# 13_HDMI_TX_RTC.net
KiCad netlist of a schematic drawn in Altium Designer
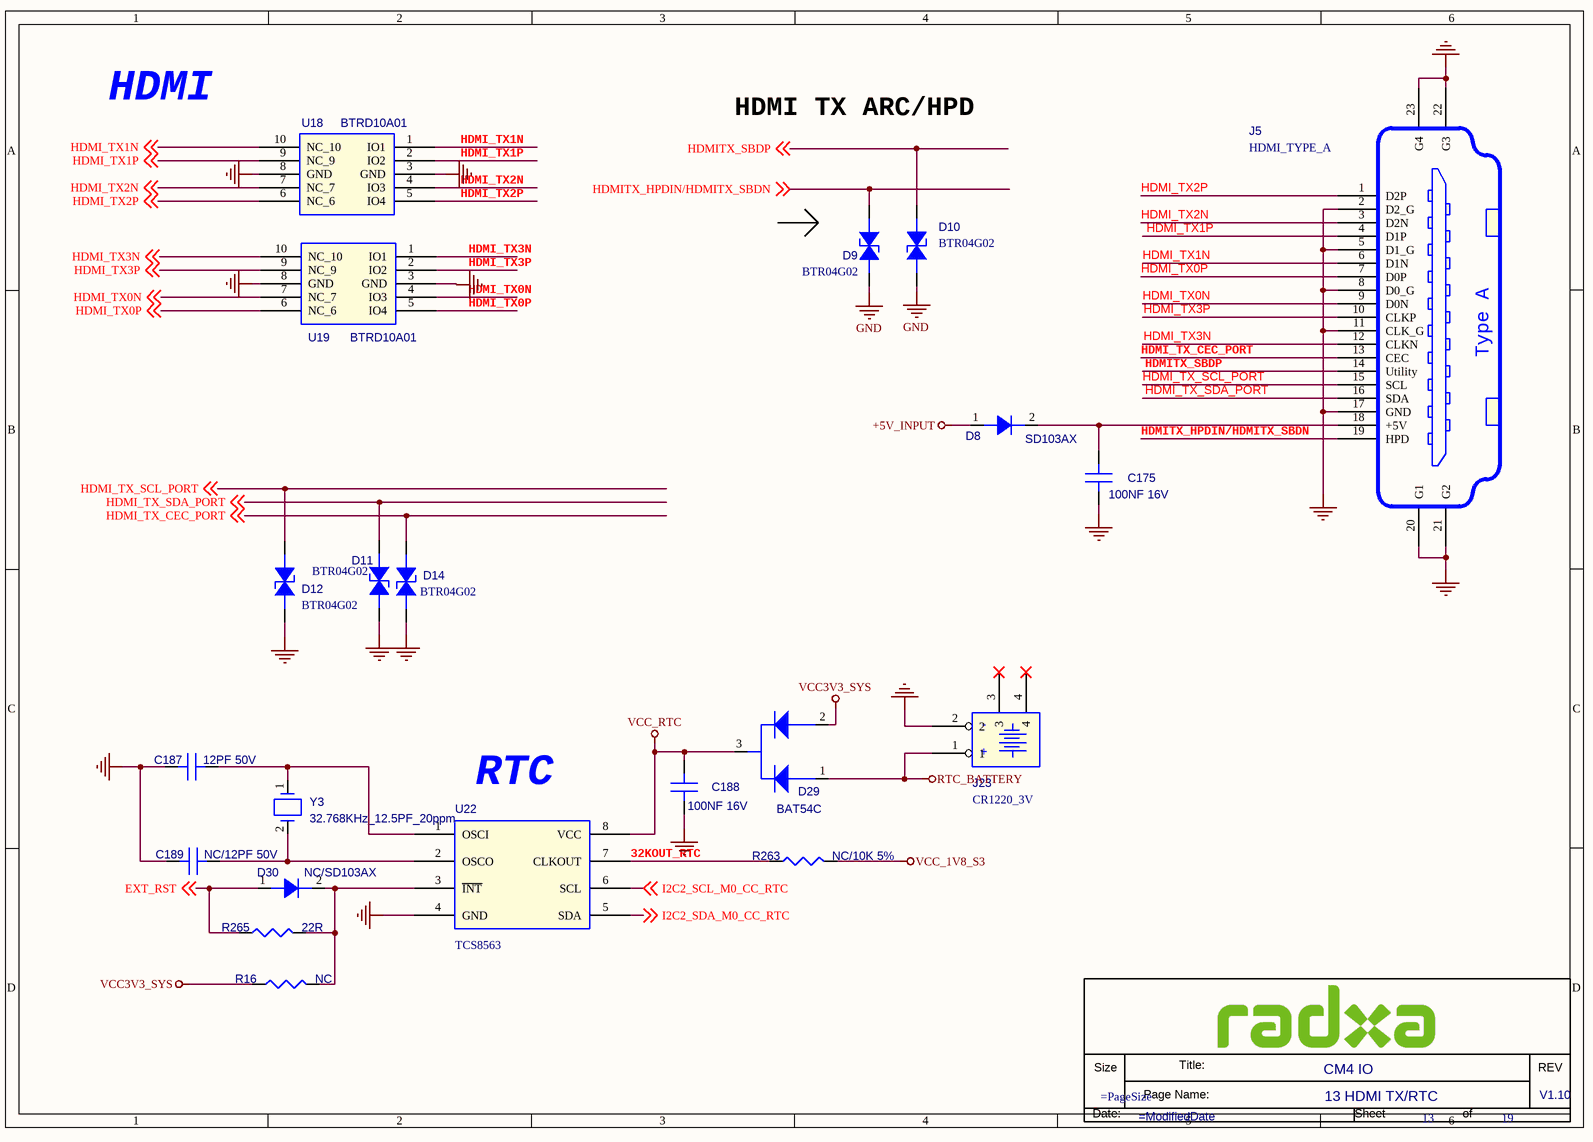
[diagram p0: 13 HDMI TX_RTC.SchDoc]

(export (version "E")
  (design (tool "Eeschema 10.0.6"))
  (components
    (comp (ref "C175")
      (value "100NF 16V")
      (footprint "C0201")
      (description "SMD  0201  100NF  16V  X5R  ±20%  ROHS")
      (fields (field (name "PART NUMBER") "A1C01.00099"))
      (libsource (lib "*") (part "C"))
    )
    (comp (ref "C187")
      (value "12PF 50V")
      (footprint "C0201")
      (description "SMD  0201  12PF  50V  COG  ±5%  ROHS")
      (fields (field (name "PART NUMBER") "A1C01.00105"))
      (libsource (lib "*") (part "C"))
    )
    (comp (ref "C188")
      (value "100NF 16V")
      (footprint "C0201")
      (description "SMD  0201  100NF  16V  X5R  ±20%  ROHS")
      (fields (field (name "PART NUMBER") "A1C01.00099"))
      (libsource (lib "*") (part "C"))
    )
    (comp (ref "C189")
      (value "NC/12PF 50V")
      (footprint "C0201")
      (description "SMD  0201  12PF  50V  COG  ±5%  ROHS")
      (fields (field (name "PART NUMBER") "A1C01.00105"))
      (libsource (lib "*") (part "C"))
    )
    (comp (ref "D8")
      (value "SD103AX")
      (footprint "SOD_523")
      (description "SMD  编带  SOD-523  SD103AX  CJ  ROHS")
      (fields
        (field (name "PART NUMBER") "A1D02.00049")
        (field (name "MANUFACTURER") "长电")
        (field (name "CREATED BY") "JJJ")
      )
      (libsource (lib "*") (part "DIODE_Dup1"))
    )
    (comp (ref "D9")
      (value "BTR04G02")
      (footprint "DFN1006-2L")
      (description "SMD  编带  0402  BTR04G02  B-tron  ROHS")
      (fields (field (name "PART NUMBER") "A1D02.00002"))
      (libsource (lib "*") (part "ESD"))
    )
    (comp (ref "D10")
      (value "BTR04G02")
      (footprint "DFN1006-2L")
      (description "SMD  编带  0402  BTR04G02  B-tron  ROHS")
      (fields (field (name "PART NUMBER") "A1D02.00002"))
      (libsource (lib "*") (part "ESD"))
    )
    (comp (ref "D11")
      (value "BTR04G02")
      (footprint "DFN1006-2L")
      (description "SMD  编带  0402  BTR04G02  B-tron  ROHS")
      (fields (field (name "PART NUMBER") "A1D02.00002"))
      (libsource (lib "*") (part "ESD"))
    )
    (comp (ref "D12")
      (value "BTR04G02")
      (footprint "DFN1006-2L")
      (description "SMD  编带  0402  BTR04G02  B-tron  ROHS")
      (fields (field (name "PART NUMBER") "A1D02.00002"))
      (libsource (lib "*") (part "ESD"))
    )
    (comp (ref "D14")
      (value "BTR04G02")
      (footprint "DFN1006-2L")
      (description "SMD  编带  0402  BTR04G02  B-tron  ROHS")
      (fields (field (name "PART NUMBER") "A1D02.00002"))
      (libsource (lib "*") (part "ESD"))
    )
    (comp (ref "D29")
      (value "BAT54C")
      (footprint "23ACA")
      (description "SMD  编带  SOT-23  BAT54C  30V  0.2A  长电  ROHS")
      (fields (field (name "PART NUMBER") "A1D02.00096"))
      (libsource (lib "*") (part "DIODE_S_3P"))
    )
    (comp (ref "D30")
      (value "NC/SD103AX")
      (footprint "SOD_523")
      (description "SMD  编带  SOD-523  SD103AX  CJ  ROHS")
      (fields
        (field (name "PART NUMBER") "A1D02.00049")
        (field (name "MANUFACTURER") "长电")
        (field (name "CREATED BY") "JJJ")
      )
      (libsource (lib "*") (part "DIODE_Dup1"))
    )
    (comp (ref "J5")
      (value "HDMI_TYPE_A")
      (footprint "CON_HDMI_TH_19P_STA")
      (description "DIP  TYPE-A  19PIN  180度  23*7.8*H16mm  镀镍  有定位柱  脚距6.5mm  4插件固定脚  WLDM-094E  ROHS")
      (fields (field (name "PART NUMBER") "A1J13.00003"))
      (libsource (lib "*") (part "HDMI_TYPE_A"))
    )
    (comp (ref "J23")
      (value "CR1220_3V")
      (footprint "BAT_SM2_12X2")
      (description "SMD  电池座  2PIN  15.4*14.2*4.1mm  BS-12-B2AA002  美阳  ROHS")
      (fields (field (name "PART NUMBER") "A1J14.00013"))
      (libsource (lib "*") (part "CR1220"))
    )
    (comp (ref "R16")
      (value "NC")
      (footprint "R0402")
      (description "SMD  0201  10K  1/20W  ±5%  ROHS")
      (fields (field (name "PART NUMBER") "A1R01.00012"))
      (libsource (lib "*") (part "R"))
    )
    (comp (ref "R263")
      (value "NC/10K 5%")
      (footprint "R0402")
      (description "SMD  0201  10K  1/20W  ±5%  ROHS")
      (fields (field (name "PART NUMBER") "A1R01.00012"))
      (libsource (lib "*") (part "R"))
    )
    (comp (ref "R265")
      (value "22R")
      (footprint "R0402")
      (description "SMD  0201  0R  1/20W  ±5%  ROHS")
      (fields (field (name "PART NUMBER") "A1R01.00027"))
      (libsource (lib "*") (part "R"))
    )
    (comp (ref "U18")
      (value "BTRD10A01")
      (footprint "SON10_0D5_1")
      (description "SMD  编带  DFN2510-10L  BTRD10A01  4Line  0.1pF  B-tron  ROHS")
      (fields (field (name "PART NUMBER") "A1D02.00106"))
      (libsource (lib "*") (part "BTRD10A01"))
    )
    (comp (ref "U19")
      (value "BTRD10A01")
      (footprint "SON10_0D5_1")
      (description "SMD  编带  DFN2510-10L  BTRD10A01  4Line  0.1pF  B-tron  ROHS")
      (fields (field (name "PART NUMBER") "A1D02.00106"))
      (libsource (lib "*") (part "BTRD10A01"))
    )
    (comp (ref "U22")
      (value "TCS8563")
      (footprint "MSOP8_0D65_3")
      (description "SMD  时钟  TCS8563-MH  MSOP8  TCS(汤诚)  ROHS")
      (fields (field (name "PART NUMBER") "A1I01.00268"))
      (libsource (lib "*") (part "TCS8563"))
    )
    (comp (ref "Y3")
      (value "32.768KHz_12.5PF_20ppm")
      (footprint "OSC_SM2_3D2X1D5")
      (description "SMD  编带  无源  3215  32.768KHz  12.5PF  ±20ppm  TAITIEN  XDMCZLNDDD-32.768KHz  ROHS")
      (fields (field (name "PART NUMBER") "A1Y01.00037"))
      (libsource (lib "*") (part "OSC_2P"))
    )
  )
  (nets
    (net (code "1") (name "+5V_INPUT") (class "Default")
      (node (ref "D8") (pin "1") (pinfunction "A_1") (pintype "passive"))
    )
    (net (code "2") (name "/32KOUT_RTC") (class "Default")
      (node (ref "R263") (pin "2") (pinfunction "2_2") (pintype "passive"))
      (node (ref "U22") (pin "7") (pinfunction "CLKOUT_7") (pintype "passive"))
    )
    (net (code "3") (name "EXT_RST") (class "Default")
      (node (ref "D30") (pin "1") (pinfunction "A_1") (pintype "passive"))
      (node (ref "R265") (pin "1") (pinfunction "1_1") (pintype "passive"))
    )
    (net (code "4") (name "GND") (class "Default")
      (node (ref "C175") (pin "2") (pinfunction "B_2") (pintype "passive"))
      (node (ref "C187") (pin "1") (pinfunction "A_1") (pintype "passive"))
      (node (ref "C188") (pin "2") (pinfunction "B_2") (pintype "passive"))
      (node (ref "C189") (pin "1") (pinfunction "A_1") (pintype "passive"))
      (node (ref "D10") (pin "2") (pinfunction "CATHODE_2") (pintype "passive"))
      (node (ref "D11") (pin "2") (pinfunction "CATHODE_2") (pintype "passive"))
      (node (ref "D12") (pin "2") (pinfunction "CATHODE_2") (pintype "passive"))
      (node (ref "D14") (pin "2") (pinfunction "CATHODE_2") (pintype "passive"))
      (node (ref "D9") (pin "2") (pinfunction "CATHODE_2") (pintype "passive"))
      (node (ref "J23") (pin "2") (pinfunction "2_2") (pintype "passive"))
      (node (ref "J5") (pin "11") (pinfunction "CLK_G_11") (pintype "passive"))
      (node (ref "J5") (pin "17") (pinfunction "GND_17") (pintype "passive"))
      (node (ref "J5") (pin "2") (pinfunction "D2_G_2") (pintype "passive"))
      (node (ref "J5") (pin "20") (pinfunction "G1_20") (pintype "passive"))
      (node (ref "J5") (pin "21") (pinfunction "G2_21") (pintype "passive"))
      (node (ref "J5") (pin "22") (pinfunction "G3_22") (pintype "passive"))
      (node (ref "J5") (pin "23") (pinfunction "G4_23") (pintype "passive"))
      (node (ref "J5") (pin "5") (pinfunction "D1_G_5") (pintype "passive"))
      (node (ref "J5") (pin "8") (pinfunction "D0_G_8") (pintype "passive"))
      (node (ref "U18") (pin "3") (pinfunction "GND_3") (pintype "power_in"))
      (node (ref "U18") (pin "8") (pinfunction "GND_8") (pintype "power_in"))
      (node (ref "U19") (pin "3") (pinfunction "GND_3") (pintype "power_in"))
      (node (ref "U19") (pin "8") (pinfunction "GND_8") (pintype "power_in"))
      (node (ref "U22") (pin "4") (pinfunction "GND_4") (pintype "passive"))
    )
    (net (code "5") (name "HDMITX_HPDIN{slash}HDMITX_SBDN") (class "Default")
      (node (ref "D9") (pin "1") (pinfunction "ANODE_1") (pintype "passive"))
      (node (ref "J5") (pin "19") (pinfunction "HPD_19") (pintype "passive"))
    )
    (net (code "6") (name "HDMITX_SBDP") (class "Default")
      (node (ref "D10") (pin "1") (pinfunction "ANODE_1") (pintype "passive"))
      (node (ref "J5") (pin "14") (pinfunction "Utility_14") (pintype "passive"))
    )
    (net (code "7") (name "HDMI_TX0N") (class "Default")
      (node (ref "J5") (pin "9") (pinfunction "D0N_9") (pintype "passive"))
      (node (ref "U19") (pin "4") (pinfunction "IO3_4") (pintype "passive"))
      (node (ref "U19") (pin "7") (pinfunction "NC_7_7") (pintype "passive"))
    )
    (net (code "8") (name "HDMI_TX0P") (class "Default")
      (node (ref "J5") (pin "7") (pinfunction "D0P_7") (pintype "passive"))
      (node (ref "U19") (pin "5") (pinfunction "IO4_5") (pintype "passive"))
      (node (ref "U19") (pin "6") (pinfunction "NC_6_6") (pintype "passive"))
    )
    (net (code "9") (name "HDMI_TX1N") (class "Default")
      (node (ref "J5") (pin "6") (pinfunction "D1N_6") (pintype "passive"))
      (node (ref "U18") (pin "1") (pinfunction "IO1_1") (pintype "passive"))
      (node (ref "U18") (pin "10") (pinfunction "NC_10_10") (pintype "passive"))
    )
    (net (code "10") (name "HDMI_TX1P") (class "Default")
      (node (ref "J5") (pin "4") (pinfunction "D1P_4") (pintype "passive"))
      (node (ref "U18") (pin "2") (pinfunction "IO2_2") (pintype "passive"))
      (node (ref "U18") (pin "9") (pinfunction "NC_9_9") (pintype "passive"))
    )
    (net (code "11") (name "HDMI_TX2N") (class "Default")
      (node (ref "J5") (pin "3") (pinfunction "D2N_3") (pintype "passive"))
      (node (ref "U18") (pin "4") (pinfunction "IO3_4") (pintype "passive"))
      (node (ref "U18") (pin "7") (pinfunction "NC_7_7") (pintype "passive"))
    )
    (net (code "12") (name "HDMI_TX2P") (class "Default")
      (node (ref "J5") (pin "1") (pinfunction "D2P_1") (pintype "passive"))
      (node (ref "U18") (pin "5") (pinfunction "IO4_5") (pintype "passive"))
      (node (ref "U18") (pin "6") (pinfunction "NC_6_6") (pintype "passive"))
    )
    (net (code "13") (name "HDMI_TX3N") (class "Default")
      (node (ref "J5") (pin "12") (pinfunction "CLKN_12") (pintype "passive"))
      (node (ref "U19") (pin "1") (pinfunction "IO1_1") (pintype "passive"))
      (node (ref "U19") (pin "10") (pinfunction "NC_10_10") (pintype "passive"))
    )
    (net (code "14") (name "HDMI_TX3P") (class "Default")
      (node (ref "J5") (pin "10") (pinfunction "CLKP_10") (pintype "passive"))
      (node (ref "U19") (pin "2") (pinfunction "IO2_2") (pintype "passive"))
      (node (ref "U19") (pin "9") (pinfunction "NC_9_9") (pintype "passive"))
    )
    (net (code "15") (name "HDMI_TX_CEC_PORT") (class "Default")
      (node (ref "D14") (pin "1") (pinfunction "ANODE_1") (pintype "passive"))
      (node (ref "J5") (pin "13") (pinfunction "CEC_13") (pintype "passive"))
    )
    (net (code "16") (name "HDMI_TX_SCL_PORT") (class "Default")
      (node (ref "D12") (pin "1") (pinfunction "ANODE_1") (pintype "passive"))
      (node (ref "J5") (pin "15") (pinfunction "SCL_15") (pintype "passive"))
    )
    (net (code "17") (name "HDMI_TX_SDA_PORT") (class "Default")
      (node (ref "D11") (pin "1") (pinfunction "ANODE_1") (pintype "passive"))
      (node (ref "J5") (pin "16") (pinfunction "SDA_16") (pintype "passive"))
    )
    (net (code "18") (name "I2C2_SCL_M0_CC_RTC") (class "Default")
      (node (ref "U22") (pin "6") (pinfunction "SCL_6") (pintype "passive"))
    )
    (net (code "19") (name "I2C2_SDA_M0_CC_RTC") (class "Default")
      (node (ref "U22") (pin "5") (pinfunction "SDA_5") (pintype "passive"))
    )
    (net (code "20") (name "Net-(C175-A)") (class "Default")
      (node (ref "C175") (pin "1") (pinfunction "A_1") (pintype "passive"))
      (node (ref "D8") (pin "2") (pinfunction "K_2") (pintype "passive"))
      (node (ref "J5") (pin "18") (pinfunction "+5V_18") (pintype "passive"))
    )
    (net (code "21") (name "Net-(C187-B)") (class "Default")
      (node (ref "C187") (pin "2") (pinfunction "B_2") (pintype "passive"))
      (node (ref "U22") (pin "1") (pinfunction "OSCI_1") (pintype "passive"))
      (node (ref "Y3") (pin "1") (pinfunction "1_1") (pintype "passive"))
    )
    (net (code "22") (name "Net-(C189-B)") (class "Default")
      (node (ref "C189") (pin "2") (pinfunction "B_2") (pintype "passive"))
      (node (ref "U22") (pin "2") (pinfunction "OSCO_2") (pintype "passive"))
      (node (ref "Y3") (pin "2") (pinfunction "2_2") (pintype "passive"))
    )
    (net (code "23") (name "Net-(D30-K)") (class "Default")
      (node (ref "D30") (pin "2") (pinfunction "K_2") (pintype "passive"))
      (node (ref "R16") (pin "2") (pinfunction "2_2") (pintype "passive"))
      (node (ref "R265") (pin "2") (pinfunction "2_2") (pintype "passive"))
      (node (ref "U22") (pin "3") (pinfunction "~{INT}_3") (pintype "passive"))
    )
    (net (code "24") (name "RTC_BATTERY") (class "Default")
      (node (ref "D29") (pin "1") (pinfunction "A1_1") (pintype "passive"))
      (node (ref "J23") (pin "1") (pinfunction "1_1") (pintype "passive"))
    )
    (net (code "25") (name "VCC3V3_SYS") (class "Default")
      (node (ref "D29") (pin "2") (pinfunction "A2_2") (pintype "passive"))
      (node (ref "R16") (pin "1") (pinfunction "1_1") (pintype "passive"))
    )
    (net (code "26") (name "VCC_1V8_S3") (class "Default")
      (node (ref "R263") (pin "1") (pinfunction "1_1") (pintype "passive"))
    )
    (net (code "27") (name "VCC_RTC") (class "Default")
      (node (ref "C188") (pin "1") (pinfunction "A_1") (pintype "passive"))
      (node (ref "D29") (pin "3") (pinfunction "C_3") (pintype "passive"))
      (node (ref "U22") (pin "8") (pinfunction "VCC_8") (pintype "passive"))
    )
    (net (code "28") (name "unconnected-(J23-Pad3)") (class "Default")
      (node (ref "J23") (pin "3") (pinfunction "3_3") (pintype "passive+no_connect"))
    )
    (net (code "29") (name "unconnected-(J23-Pad4)") (class "Default")
      (node (ref "J23") (pin "4") (pinfunction "4_4") (pintype "passive+no_connect"))
    )
  )
)
